# Carte_Alim_2019_TRACO.net
KiCad netlist of a schematic drawn in Altium Designer
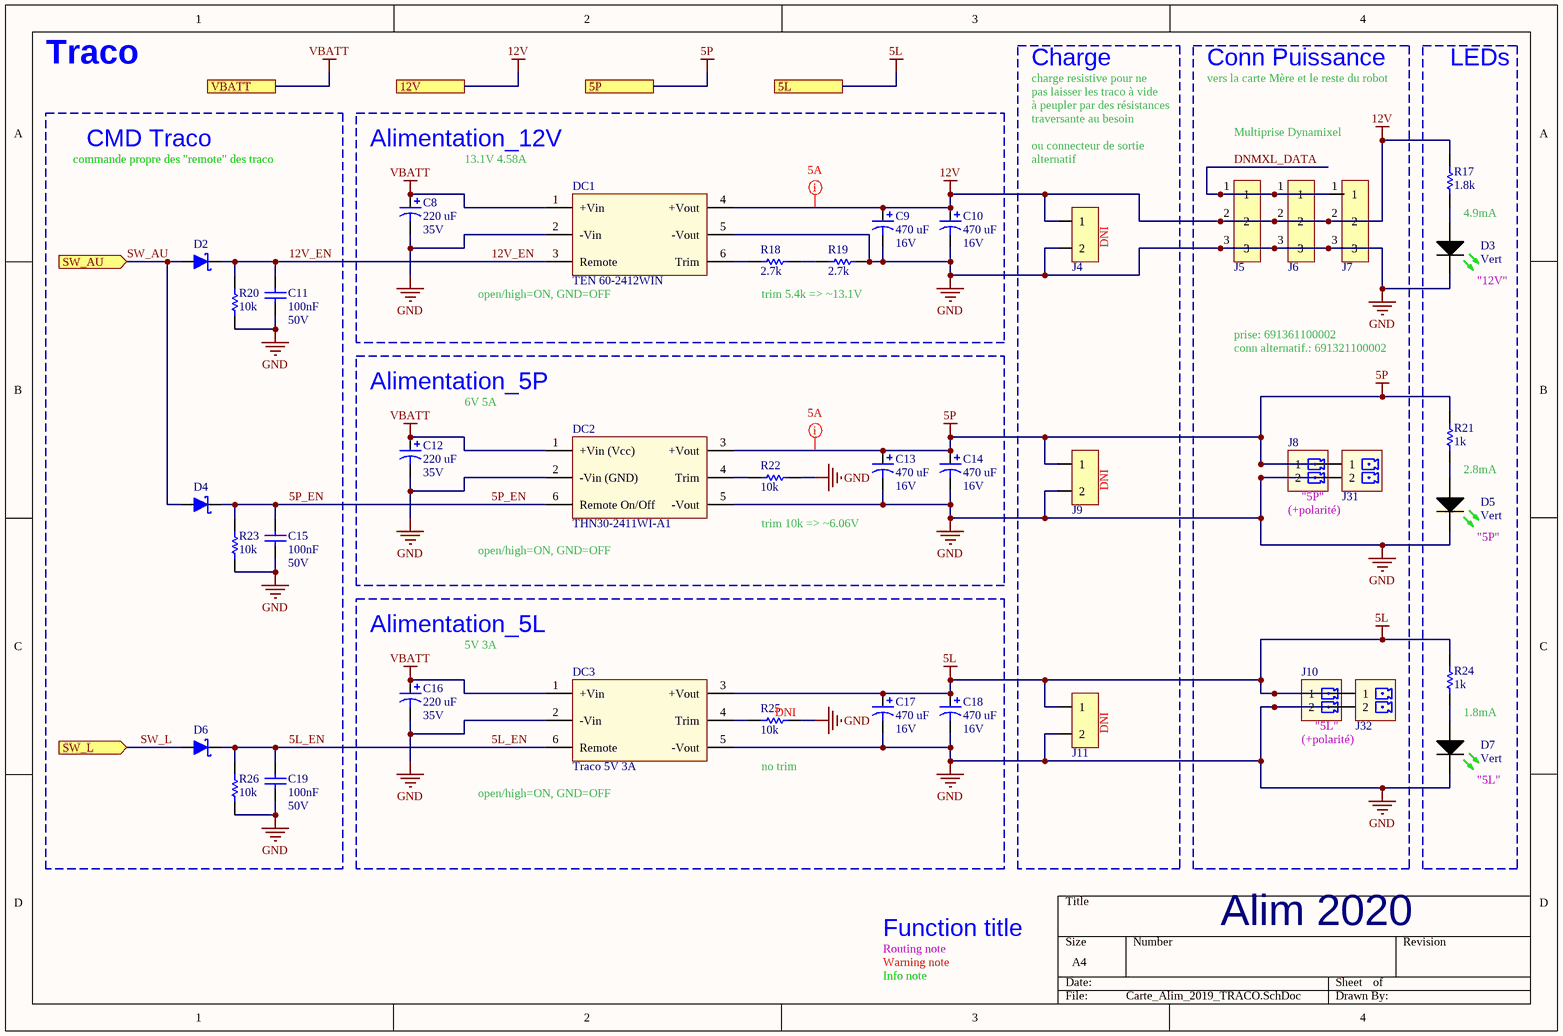
[diagram p0: Carte_Alim_2019_TRACO.SchDoc]

(export (version "E")
  (design (tool "Eeschema 10.0.6"))
  (components
    (comp (ref "C8")
      (value "220 uF")
      (footprint "WCAP-ATG8_8x11.5x3.5x0.5")
      (description "CAP Alu 220 UF 20% 35 V")
      (fields
        (field (name "MANUFACTURER") "Wurth Elektronik")
        (field (name "MANUFACTURER PART NUMBER") "860010574011")
        (field (name "RATEDVOLTAGE") "35V")
      )
      (libsource (lib "Condensateur") (part "WCAP-ATG8, 860010574011"))
    )
    (comp (ref "C9")
      (value "470 uF")
      (footprint "WCAP-ATG8_8x11.5x3.5x0.5")
      (description "CAP Alu 470 UF 20% 16 V")
      (fields
        (field (name "MANUFACTURER") "Wurth Elektronik")
        (field (name "MANUFACTURER PART NUMBER") "860010374012")
        (field (name "RATEDVOLTAGE") "16V")
      )
      (libsource (lib "Condensateur") (part "WCAP-ATG8, 860010374012"))
    )
    (comp (ref "C10")
      (value "470 uF")
      (footprint "WCAP-ATG8_8x11.5x3.5x0.5")
      (description "CAP Alu 470 UF 20% 16 V")
      (fields
        (field (name "MANUFACTURER") "Wurth Elektronik")
        (field (name "MANUFACTURER PART NUMBER") "860010374012")
        (field (name "RATEDVOLTAGE") "16V")
      )
      (libsource (lib "Condensateur") (part "WCAP-ATG8, 860010374012"))
    )
    (comp (ref "C11")
      (value "100nF")
      (footprint "WCAP-CSGP_0603, 1.6x0.8x0.8")
      (description "CAP CER 100nF 50V X7R 0603")
      (fields
        (field (name "RATEDVOLTAGE") "50V")
        (field (name "MANUFACTURER") "Wurth Elektronik")
        (field (name "MANUFACTURER PART NUMBER") "885012206095")
      )
      (libsource (lib "Condensateur") (part "WCAP-CSGP, 885012206095"))
    )
    (comp (ref "C12")
      (value "220 uF")
      (footprint "WCAP-ATG8_8x11.5x3.5x0.5")
      (description "CAP Alu 220 UF 20% 35 V")
      (fields
        (field (name "MANUFACTURER") "Wurth Elektronik")
        (field (name "MANUFACTURER PART NUMBER") "860010574011")
        (field (name "RATEDVOLTAGE") "35V")
      )
      (libsource (lib "Condensateur") (part "WCAP-ATG8, 860010574011"))
    )
    (comp (ref "C13")
      (value "470 uF")
      (footprint "WCAP-ATG8_8x11.5x3.5x0.5")
      (description "CAP Alu 470 UF 20% 16 V")
      (fields
        (field (name "MANUFACTURER") "Wurth Elektronik")
        (field (name "MANUFACTURER PART NUMBER") "860010374012")
        (field (name "RATEDVOLTAGE") "16V")
      )
      (libsource (lib "Condensateur") (part "WCAP-ATG8, 860010374012"))
    )
    (comp (ref "C14")
      (value "470 uF")
      (footprint "WCAP-ATG8_8x11.5x3.5x0.5")
      (description "CAP Alu 470 UF 20% 16 V")
      (fields
        (field (name "MANUFACTURER") "Wurth Elektronik")
        (field (name "MANUFACTURER PART NUMBER") "860010374012")
        (field (name "RATEDVOLTAGE") "16V")
      )
      (libsource (lib "Condensateur") (part "WCAP-ATG8, 860010374012"))
    )
    (comp (ref "C15")
      (value "100nF")
      (footprint "WCAP-CSGP_0603, 1.6x0.8x0.8")
      (description "CAP CER 100nF 50V X7R 0603")
      (fields
        (field (name "RATEDVOLTAGE") "50V")
        (field (name "MANUFACTURER") "Wurth Elektronik")
        (field (name "MANUFACTURER PART NUMBER") "885012206095")
      )
      (libsource (lib "Condensateur") (part "WCAP-CSGP, 885012206095"))
    )
    (comp (ref "C16")
      (value "220 uF")
      (footprint "WCAP-ATG8_8x11.5x3.5x0.5")
      (description "CAP Alu 220 UF 20% 35 V")
      (fields
        (field (name "MANUFACTURER") "Wurth Elektronik")
        (field (name "MANUFACTURER PART NUMBER") "860010574011")
        (field (name "RATEDVOLTAGE") "35V")
      )
      (libsource (lib "Condensateur") (part "WCAP-ATG8, 860010574011"))
    )
    (comp (ref "C17")
      (value "470 uF")
      (footprint "WCAP-ATG8_8x11.5x3.5x0.5")
      (description "CAP Alu 470 UF 20% 16 V")
      (fields
        (field (name "MANUFACTURER") "Wurth Elektronik")
        (field (name "MANUFACTURER PART NUMBER") "860010374012")
        (field (name "RATEDVOLTAGE") "16V")
      )
      (libsource (lib "Condensateur") (part "WCAP-ATG8, 860010374012"))
    )
    (comp (ref "C18")
      (value "470 uF")
      (footprint "WCAP-ATG8_8x11.5x3.5x0.5")
      (description "CAP Alu 470 UF 20% 16 V")
      (fields
        (field (name "MANUFACTURER") "Wurth Elektronik")
        (field (name "MANUFACTURER PART NUMBER") "860010374012")
        (field (name "RATEDVOLTAGE") "16V")
      )
      (libsource (lib "Condensateur") (part "WCAP-ATG8, 860010374012"))
    )
    (comp (ref "C19")
      (value "100nF")
      (footprint "WCAP-CSGP_0603, 1.6x0.8x0.8")
      (description "CAP CER 100nF 50V X7R 0603")
      (fields
        (field (name "RATEDVOLTAGE") "50V")
        (field (name "MANUFACTURER") "Wurth Elektronik")
        (field (name "MANUFACTURER PART NUMBER") "885012206095")
      )
      (libsource (lib "Condensateur") (part "WCAP-CSGP, 885012206095"))
    )
    (comp (ref "D2")
      (value "RBR3MM40ATFTR")
      (footprint "SOD-123FL")
      (description "DIODE SCHOTTKY 40V 3A SOD123-FL")
      (fields (field (name "MANUFACTURER") "ROHM"))
      (libsource (lib "Diode") (part "RBR3MM40ATFTR"))
    )
    (comp (ref "D3")
      (value "Vert")
      (footprint "SMCW_0603")
      (description "SMD mono-color Chip LED, WL-SMCW, Green")
      (fields
        (field (name "MANUFACTURER PART NUMBER") "150060GS75000")
        (field (name "CREATED BY") "Christin Otto")
      )
      (libsource (lib "Optoélectronique") (part "WL-SMCW 0603  150060GS75000"))
    )
    (comp (ref "D4")
      (value "RBR3MM40ATFTR")
      (footprint "SOD-123FL")
      (description "DIODE SCHOTTKY 40V 3A SOD123-FL")
      (fields (field (name "MANUFACTURER") "ROHM"))
      (libsource (lib "Diode") (part "RBR3MM40ATFTR"))
    )
    (comp (ref "D5")
      (value "Vert")
      (footprint "SMCW_0603")
      (description "SMD mono-color Chip LED, WL-SMCW, Green")
      (fields
        (field (name "MANUFACTURER PART NUMBER") "150060GS75000")
        (field (name "CREATED BY") "Christin Otto")
      )
      (libsource (lib "Optoélectronique") (part "WL-SMCW 0603  150060GS75000"))
    )
    (comp (ref "D6")
      (value "RBR3MM40ATFTR")
      (footprint "SOD-123FL")
      (description "DIODE SCHOTTKY 40V 3A SOD123-FL")
      (fields (field (name "MANUFACTURER") "ROHM"))
      (libsource (lib "Diode") (part "RBR3MM40ATFTR"))
    )
    (comp (ref "D7")
      (value "Vert")
      (footprint "SMCW_0603")
      (description "SMD mono-color Chip LED, WL-SMCW, Green")
      (fields
        (field (name "MANUFACTURER PART NUMBER") "150060GS75000")
        (field (name "CREATED BY") "Christin Otto")
      )
      (libsource (lib "Optoélectronique") (part "WL-SMCW 0603  150060GS75000"))
    )
    (comp (ref "DC1")
      (value "TEN 60-2412WIN")
      (footprint "TEN 60")
      (description "Traco 12.0V 60W 5A")
      (fields (field (name "MANUFACTURER") "TRACOPOWER"))
      (libsource (lib "Alimentation") (part "TEN 60-2412WIN"))
    )
    (comp (ref "DC2")
      (value "THN30-2411WI-A1")
      (footprint "THN 30WI-A1")
      (description "Traco 5V-6V 30W 6A")
      (fields (field (name "MANUFACTURER") "TRACOPOWER"))
      (libsource (lib "Alimentation") (part "THN30-2411WI-A1"))
    )
    (comp (ref "DC3")
      (value "Traco 5V 3A")
      (footprint "THN 15WI")
      (description "Traco 5V 15W 3A")
      (fields
        (field (name "MANUFACTURER") "TRACOPOWER")
        (field (name "MANUFACTURER PART NUMBER") "THN15-2411WI")
      )
      (libsource (lib "Alimentation") (part "THN15-2411WI"))
    )
    (comp (ref "J4")
      (value "22-03-2021")
      (footprint "22-03-2021")
      (libsource (lib "Connecteurs") (part "22-03-2021"))
    )
    (comp (ref "J5")
      (value "22-03-5035")
      (footprint "20-03-5035")
      (libsource (lib "Connecteurs") (part "20-03-5035"))
    )
    (comp (ref "J6")
      (value "22-03-5035")
      (footprint "20-03-5035")
      (libsource (lib "Connecteurs") (part "20-03-5035"))
    )
    (comp (ref "J7")
      (value "22-03-5035")
      (footprint "20-03-5035")
      (libsource (lib "Connecteurs") (part "20-03-5035"))
    )
    (comp (ref "J8")
      (value "691322110002")
      (footprint "691322110002")
      (description "WR-TBL 2p Series 3221 - 3.50 mm Horizontal PCB Header")
      (fields (field (name "MANUFACTURER") "Wurth Electronics Inc."))
      (libsource (lib "Connecteurs") (part "691322110002"))
    )
    (comp (ref "J9")
      (value "22-03-2021")
      (footprint "22-03-2021")
      (libsource (lib "Connecteurs") (part "22-03-2021"))
    )
    (comp (ref "J10")
      (value "691322110002")
      (footprint "691322110002")
      (description "WR-TBL 2p Series 3221 - 3.50 mm Horizontal PCB Header")
      (fields (field (name "MANUFACTURER") "Wurth Electronics Inc."))
      (libsource (lib "Connecteurs") (part "691322110002"))
    )
    (comp (ref "J11")
      (value "22-03-2021")
      (footprint "22-03-2021")
      (libsource (lib "Connecteurs") (part "22-03-2021"))
    )
    (comp (ref "J31")
      (value "691321100002")
      (footprint "691321100002")
      (description "WR-TBL 2p Series 3211 - 3.50 mm Vertical PCB Header")
      (fields (field (name "MANUFACTURER") "Wurth Electronics Inc."))
      (libsource (lib "Connecteurs") (part "691321100002"))
    )
    (comp (ref "J32")
      (value "691321100002")
      (footprint "691321100002")
      (description "WR-TBL 2p Series 3211 - 3.50 mm Vertical PCB Header")
      (fields (field (name "MANUFACTURER") "Wurth Electronics Inc."))
      (libsource (lib "Connecteurs") (part "691321100002"))
    )
    (comp (ref "R17")
      (value "1.8k")
      (footprint "RESC1608X06N")
      (description "RES SMD 1.8K OHM 1% 1/10W 0603")
      (fields
        (field (name "MANUFACTURER") "Yageo")
        (field (name "MANUFACTURER PART NUMBER") "RC0603FR-071K8L")
      )
      (libsource (lib "Resistance") (part "RC0603FR-071K8L"))
    )
    (comp (ref "R18")
      (value "2.7k")
      (footprint "RESC2012X06M")
      (description "RES SMD 2K7 OHM 1% 1/8W 0805")
      (fields
        (field (name "MANUFACTURER") "Yageo")
        (field (name "MANUFACTURER PART NUMBER") "RC0805FR-072K7L")
      )
      (libsource (lib "Resistance") (part "RC0805FR-072K7L"))
    )
    (comp (ref "R19")
      (value "2.7k")
      (footprint "RESC2012X06M")
      (description "RES SMD 2K7 OHM 1% 1/8W 0805")
      (fields
        (field (name "MANUFACTURER") "Yageo")
        (field (name "MANUFACTURER PART NUMBER") "RC0805FR-072K7L")
      )
      (libsource (lib "Resistance") (part "RC0805FR-072K7L"))
    )
    (comp (ref "R20")
      (value "10k")
      (footprint "RESC1608X06N")
      (description "RES SMD 10K OHM 1% 1/10W 0603")
      (fields
        (field (name "MANUFACTURER") "Yageo")
        (field (name "MANUFACTURER PART NUMBER") "RC0603FR-0710KL")
      )
      (libsource (lib "Resistance") (part "RC0603FR-0710KL"))
    )
    (comp (ref "R21")
      (value "1k")
      (footprint "RESC1608X06N")
      (description "RES SMD 1K OHM 1% 1/10W 0603")
      (fields
        (field (name "MANUFACTURER") "Yageo")
        (field (name "MANUFACTURER PART NUMBER") "RC0603FR-071KL")
      )
      (libsource (lib "Resistance") (part "RC0603FR-071KL"))
    )
    (comp (ref "R22")
      (value "10k")
      (footprint "RESC1608X06N")
      (description "RES SMD 10K OHM 1% 1/10W 0603")
      (fields
        (field (name "MANUFACTURER") "Yageo")
        (field (name "MANUFACTURER PART NUMBER") "RC0603FR-0710KL")
      )
      (libsource (lib "Resistance") (part "RC0603FR-0710KL"))
    )
    (comp (ref "R23")
      (value "10k")
      (footprint "RESC1608X06N")
      (description "RES SMD 10K OHM 1% 1/10W 0603")
      (fields
        (field (name "MANUFACTURER") "Yageo")
        (field (name "MANUFACTURER PART NUMBER") "RC0603FR-0710KL")
      )
      (libsource (lib "Resistance") (part "RC0603FR-0710KL"))
    )
    (comp (ref "R24")
      (value "1k")
      (footprint "RESC1608X06N")
      (description "RES SMD 1K OHM 1% 1/10W 0603")
      (fields
        (field (name "MANUFACTURER") "Yageo")
        (field (name "MANUFACTURER PART NUMBER") "RC0603FR-071KL")
      )
      (libsource (lib "Resistance") (part "RC0603FR-071KL"))
    )
    (comp (ref "R25")
      (value "10k")
      (footprint "RESC1608X06N")
      (description "RES SMD 10K OHM 1% 1/10W 0603")
      (fields
        (field (name "MANUFACTURER") "Yageo")
        (field (name "MANUFACTURER PART NUMBER") "RC0603FR-0710KL")
      )
      (libsource (lib "Resistance") (part "RC0603FR-0710KL"))
    )
    (comp (ref "R26")
      (value "10k")
      (footprint "RESC1608X06N")
      (description "RES SMD 10K OHM 1% 1/10W 0603")
      (fields
        (field (name "MANUFACTURER") "Yageo")
        (field (name "MANUFACTURER PART NUMBER") "RC0603FR-0710KL")
      )
      (libsource (lib "Resistance") (part "RC0603FR-0710KL"))
    )
  )
  (nets
    (net (code "1") (name "/5L_EN") (class "Default")
      (node (ref "C19") (pin "2") (pinfunction "2_2") (pintype "passive"))
      (node (ref "D6") (pin "2") (pintype "passive"))
      (node (ref "DC3") (pin "6") (pinfunction "Remote_6") (pintype "power_in"))
      (node (ref "R26") (pin "2") (pinfunction "2_2") (pintype "passive"))
    )
    (net (code "2") (name "/5P_EN") (class "Default")
      (node (ref "C15") (pin "2") (pinfunction "2_2") (pintype "passive"))
      (node (ref "D4") (pin "2") (pintype "passive"))
      (node (ref "DC2") (pin "6") (pinfunction "Remote_On/Off_6") (pintype "power_in"))
      (node (ref "R23") (pin "2") (pinfunction "2_2") (pintype "passive"))
    )
    (net (code "3") (name "/12V_EN") (class "Default")
      (node (ref "C11") (pin "2") (pinfunction "2_2") (pintype "passive"))
      (node (ref "D2") (pin "2") (pintype "passive"))
      (node (ref "DC1") (pin "3") (pinfunction "Remote_3") (pintype "power_in"))
      (node (ref "R20") (pin "2") (pinfunction "2_2") (pintype "passive"))
    )
    (net (code "4") (name "/DNMXL_DATA") (class "Default")
      (node (ref "J5") (pin "1") (pinfunction "1_1") (pintype "passive"))
      (node (ref "J6") (pin "1") (pinfunction "1_1") (pintype "passive"))
      (node (ref "J7") (pin "1") (pinfunction "1_1") (pintype "passive"))
    )
    (net (code "5") (name "/SW_AU") (class "Default")
      (node (ref "D2") (pin "1") (pintype "passive"))
      (node (ref "D4") (pin "1") (pintype "passive"))
    )
    (net (code "6") (name "/SW_L") (class "Default") (node (ref "D6") (pin "1") (pintype "passive")))
    (net (code "7") (name "5L") (class "Default")
      (node (ref "C17") (pin "1") (pinfunction "1_1") (pintype "passive"))
      (node (ref "C18") (pin "1") (pinfunction "1_1") (pintype "passive"))
      (node (ref "DC3") (pin "3") (pinfunction "+Vout_3") (pintype "power_in"))
      (node (ref "J10") (pin "1") (pinfunction "1_1") (pintype "passive"))
      (node (ref "J11") (pin "1") (pinfunction "1_1") (pintype "passive"))
      (node (ref "J32") (pin "1") (pinfunction "1_1") (pintype "passive"))
      (node (ref "R24") (pin "1") (pinfunction "1_1") (pintype "passive"))
    )
    (net (code "8") (name "5P") (class "Default")
      (node (ref "C13") (pin "1") (pinfunction "1_1") (pintype "passive"))
      (node (ref "C14") (pin "1") (pinfunction "1_1") (pintype "passive"))
      (node (ref "DC2") (pin "3") (pinfunction "+Vout_3") (pintype "power_in"))
      (node (ref "J31") (pin "1") (pinfunction "1_1") (pintype "passive"))
      (node (ref "J8") (pin "1") (pinfunction "1_1") (pintype "passive"))
      (node (ref "J9") (pin "1") (pinfunction "1_1") (pintype "passive"))
      (node (ref "R21") (pin "1") (pinfunction "1_1") (pintype "passive"))
    )
    (net (code "9") (name "12V") (class "Default")
      (node (ref "C10") (pin "1") (pinfunction "1_1") (pintype "passive"))
      (node (ref "C9") (pin "1") (pinfunction "1_1") (pintype "passive"))
      (node (ref "DC1") (pin "4") (pinfunction "+Vout_4") (pintype "power_in"))
      (node (ref "J4") (pin "1") (pinfunction "1_1") (pintype "passive"))
      (node (ref "J5") (pin "2") (pinfunction "2_2") (pintype "passive"))
      (node (ref "J6") (pin "2") (pinfunction "2_2") (pintype "passive"))
      (node (ref "J7") (pin "2") (pinfunction "2_2") (pintype "passive"))
      (node (ref "R17") (pin "2") (pinfunction "2_2") (pintype "passive"))
    )
    (net (code "10") (name "GND") (class "Default")
      (node (ref "C10") (pin "2") (pinfunction "2_2") (pintype "passive"))
      (node (ref "C11") (pin "1") (pinfunction "1_1") (pintype "passive"))
      (node (ref "C12") (pin "2") (pinfunction "2_2") (pintype "passive"))
      (node (ref "C13") (pin "2") (pinfunction "2_2") (pintype "passive"))
      (node (ref "C14") (pin "2") (pinfunction "2_2") (pintype "passive"))
      (node (ref "C15") (pin "1") (pinfunction "1_1") (pintype "passive"))
      (node (ref "C16") (pin "2") (pinfunction "2_2") (pintype "passive"))
      (node (ref "C17") (pin "2") (pinfunction "2_2") (pintype "passive"))
      (node (ref "C18") (pin "2") (pinfunction "2_2") (pintype "passive"))
      (node (ref "C19") (pin "1") (pinfunction "1_1") (pintype "passive"))
      (node (ref "C8") (pin "2") (pinfunction "2_2") (pintype "passive"))
      (node (ref "C9") (pin "2") (pinfunction "2_2") (pintype "passive"))
      (node (ref "D3") (pin "1") (pinfunction "C_1") (pintype "passive"))
      (node (ref "D5") (pin "1") (pinfunction "C_1") (pintype "passive"))
      (node (ref "D7") (pin "1") (pinfunction "C_1") (pintype "passive"))
      (node (ref "DC1") (pin "2") (pinfunction "-Vin_2") (pintype "power_in"))
      (node (ref "DC1") (pin "5") (pinfunction "-Vout_5") (pintype "power_in"))
      (node (ref "DC2") (pin "2") (pinfunction "-Vin_(GND)_2") (pintype "power_in"))
      (node (ref "DC2") (pin "5") (pinfunction "-Vout_5") (pintype "power_in"))
      (node (ref "DC3") (pin "2") (pinfunction "-Vin_2") (pintype "power_in"))
      (node (ref "DC3") (pin "5") (pinfunction "-Vout_5") (pintype "power_in"))
      (node (ref "J10") (pin "2") (pinfunction "2_2") (pintype "passive"))
      (node (ref "J11") (pin "2") (pinfunction "2_2") (pintype "passive"))
      (node (ref "J31") (pin "2") (pinfunction "2_2") (pintype "passive"))
      (node (ref "J32") (pin "2") (pinfunction "2_2") (pintype "passive"))
      (node (ref "J4") (pin "2") (pinfunction "2_2") (pintype "passive"))
      (node (ref "J5") (pin "3") (pinfunction "3_3") (pintype "passive"))
      (node (ref "J6") (pin "3") (pinfunction "3_3") (pintype "passive"))
      (node (ref "J7") (pin "3") (pinfunction "3_3") (pintype "passive"))
      (node (ref "J8") (pin "2") (pinfunction "2_2") (pintype "passive"))
      (node (ref "J9") (pin "2") (pinfunction "2_2") (pintype "passive"))
      (node (ref "R19") (pin "2") (pinfunction "2_2") (pintype "passive"))
      (node (ref "R20") (pin "1") (pinfunction "1_1") (pintype "passive"))
      (node (ref "R22") (pin "2") (pinfunction "2_2") (pintype "passive"))
      (node (ref "R23") (pin "1") (pinfunction "1_1") (pintype "passive"))
      (node (ref "R25") (pin "2") (pinfunction "2_2") (pintype "passive"))
      (node (ref "R26") (pin "1") (pinfunction "1_1") (pintype "passive"))
    )
    (net (code "11") (name "Net-(D3-A)") (class "Default")
      (node (ref "D3") (pin "2") (pinfunction "A_2") (pintype "passive"))
      (node (ref "R17") (pin "1") (pinfunction "1_1") (pintype "passive"))
    )
    (net (code "12") (name "Net-(D5-A)") (class "Default")
      (node (ref "D5") (pin "2") (pinfunction "A_2") (pintype "passive"))
      (node (ref "R21") (pin "2") (pinfunction "2_2") (pintype "passive"))
    )
    (net (code "13") (name "Net-(D7-A)") (class "Default")
      (node (ref "D7") (pin "2") (pinfunction "A_2") (pintype "passive"))
      (node (ref "R24") (pin "2") (pinfunction "2_2") (pintype "passive"))
    )
    (net (code "14") (name "Net-(DC1-Trim)") (class "Default")
      (node (ref "DC1") (pin "6") (pinfunction "Trim_6") (pintype "power_in"))
      (node (ref "R18") (pin "1") (pinfunction "1_1") (pintype "passive"))
    )
    (net (code "15") (name "Net-(DC2-Trim)") (class "Default")
      (node (ref "DC2") (pin "4") (pinfunction "Trim_4") (pintype "power_in"))
      (node (ref "R22") (pin "1") (pinfunction "1_1") (pintype "passive"))
    )
    (net (code "16") (name "Net-(DC3-Trim)") (class "Default")
      (node (ref "DC3") (pin "4") (pinfunction "Trim_4") (pintype "power_in"))
      (node (ref "R25") (pin "1") (pinfunction "1_1") (pintype "passive"))
    )
    (net (code "17") (name "Net-(R18-Pad2)") (class "Default")
      (node (ref "R18") (pin "2") (pinfunction "2_2") (pintype "passive"))
      (node (ref "R19") (pin "1") (pinfunction "1_1") (pintype "passive"))
    )
    (net (code "18") (name "VBATT") (class "Default")
      (node (ref "C12") (pin "1") (pinfunction "1_1") (pintype "passive"))
      (node (ref "C16") (pin "1") (pinfunction "1_1") (pintype "passive"))
      (node (ref "C8") (pin "1") (pinfunction "1_1") (pintype "passive"))
      (node (ref "DC1") (pin "1") (pinfunction "+Vin_1") (pintype "power_in"))
      (node (ref "DC2") (pin "1") (pinfunction "+Vin_(Vcc)_1") (pintype "power_in"))
      (node (ref "DC3") (pin "1") (pinfunction "+Vin_1") (pintype "power_in"))
    )
  )
)
